# esp.net
KiCad netlist of a schematic drawn in EAGLE
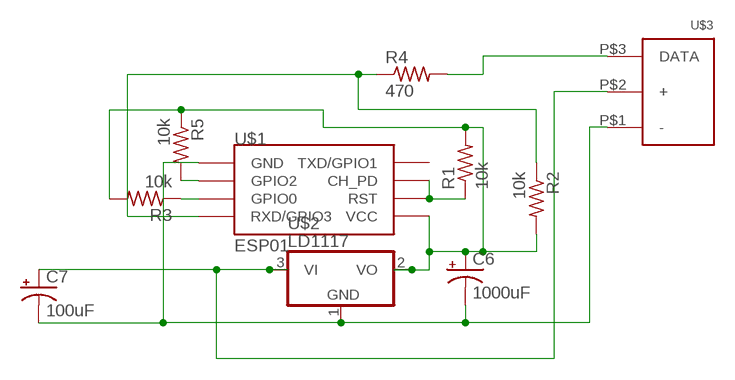
[diagram p0: schematic, sheet 1]

(export (version "E")
  (design (tool "Eeschema 10.0.6"))
  (components
    (comp (ref "C6")
      (value "1000uF")
      (footprint "eagle-import:E5-10,5")
      (libsource (lib "eagle-import") (part "CPOL-USE5-10.5"))
    )
    (comp (ref "C7")
      (value "100uF")
      (footprint "eagle-import:E2,5-6")
      (libsource (lib "eagle-import") (part "CPOL-USE2.5-6"))
    )
    (comp (ref "R1")
      (value "10k")
      (footprint "eagle-import:0204_7")
      (libsource (lib "eagle-import") (part "R-US_0204/7"))
    )
    (comp (ref "R2")
      (value "10k")
      (footprint "eagle-import:0204_7")
      (libsource (lib "eagle-import") (part "R-US_0204/7"))
    )
    (comp (ref "R3")
      (value "10k")
      (footprint "eagle-import:0204_7")
      (libsource (lib "eagle-import") (part "R-US_0204/7"))
    )
    (comp (ref "R4")
      (value "470")
      (footprint "eagle-import:0204_7")
      (libsource (lib "eagle-import") (part "R-US_0204/7"))
    )
    (comp (ref "R5")
      (value "10k")
      (footprint "eagle-import:0204_7")
      (libsource (lib "eagle-import") (part "R-US_0204/7"))
    )
    (comp (ref "U$1")
      (value "ESP01")
      (footprint "eagle-import:ESP01")
      (libsource (lib "eagle-import") (part "ESP01"))
    )
    (comp (ref "U$2")
      (value "LD1117")
      (footprint "eagle-import:TO220V")
      (libsource (lib "eagle-import") (part "LD1117"))
    )
    (comp (ref "U$3")
      (value "SERVO")
      (footprint "eagle-import:1X3")
      (libsource (lib "eagle-import") (part "SERVO"))
    )
  )
  (nets
    (net (code "1") (name "Net-(R1-Pad1)") (class "Default")
      (node (ref "R1") (pin "1") (pinfunction "1_1") (pintype "passive"))
      (node (ref "U$1") (pin "CH_PD") (pinfunction "CH_PD_CH_PD") (pintype "bidirectional"))
      (node (ref "U$1") (pin "RST") (pinfunction "RST_RST") (pintype "bidirectional"))
    )
    (net (code "2") (name "Net-(R3-Pad1)") (class "Default")
      (node (ref "R3") (pin "1") (pinfunction "1_1") (pintype "passive"))
      (node (ref "U$1") (pin "GPIO0") (pinfunction "GPIO0_GPIO0") (pintype "bidirectional"))
    )
    (net (code "3") (name "Net-(R5-Pad2)") (class "Default")
      (node (ref "R5") (pin "2") (pinfunction "2_2") (pintype "passive"))
      (node (ref "U$1") (pin "GPIO2") (pinfunction "GPIO2_GPIO2") (pintype "bidirectional"))
    )
    (net (code "4") (name "Net-(U$1-RXD{slash}GPIO3)") (class "Default")
      (node (ref "R2") (pin "1") (pinfunction "1_1") (pintype "passive"))
      (node (ref "R4") (pin "1") (pinfunction "1_1") (pintype "passive"))
      (node (ref "U$1") (pin "RX") (pinfunction "RXD/GPIO3_RX") (pintype "bidirectional"))
    )
    (net (code "5") (name "Net-(U$2-GND)") (class "Default")
      (node (ref "C6") (pin "-") (pinfunction "-_-") (pintype "passive"))
      (node (ref "C7") (pin "-") (pinfunction "-_-") (pintype "passive"))
      (node (ref "U$1") (pin "GND") (pinfunction "GND_GND") (pintype "bidirectional"))
      (node (ref "U$2") (pin "1") (pinfunction "GND_1") (pintype "passive"))
      (node (ref "U$3") (pin "P$1") (pinfunction "-_P$1") (pintype "bidirectional"))
    )
    (net (code "6") (name "Net-(U$2-VI)") (class "Default")
      (node (ref "C7") (pin "+") (pinfunction "+_+") (pintype "passive"))
      (node (ref "U$2") (pin "3") (pinfunction "VI_3") (pintype "input"))
      (node (ref "U$3") (pin "P$2") (pinfunction "+_P$2") (pintype "bidirectional"))
    )
    (net (code "7") (name "Net-(U$2-VO)") (class "Default")
      (node (ref "C6") (pin "+") (pinfunction "+_+") (pintype "passive"))
      (node (ref "R1") (pin "2") (pinfunction "2_2") (pintype "passive"))
      (node (ref "R2") (pin "2") (pinfunction "2_2") (pintype "passive"))
      (node (ref "R3") (pin "2") (pinfunction "2_2") (pintype "passive"))
      (node (ref "R5") (pin "1") (pinfunction "1_1") (pintype "passive"))
      (node (ref "U$1") (pin "VCC") (pinfunction "VCC_VCC") (pintype "bidirectional"))
      (node (ref "U$2") (pin "2") (pinfunction "VO_2") (pintype "passive"))
    )
    (net (code "8") (name "Net-(U$3-DATA)") (class "Default")
      (node (ref "R4") (pin "2") (pinfunction "2_2") (pintype "passive"))
      (node (ref "U$3") (pin "P$3") (pinfunction "DATA_P$3") (pintype "bidirectional"))
    )
    (net (code "9") (name "unconnected-(U$1-TXD{slash}GPIO1-PadTX)") (class "Default")
      (node (ref "U$1") (pin "TX") (pinfunction "TXD/GPIO1_TX") (pintype "bidirectional"))
    )
  )
)
